# PMP30825_RevB.net
KiCad netlist of a schematic drawn in Altium Designer
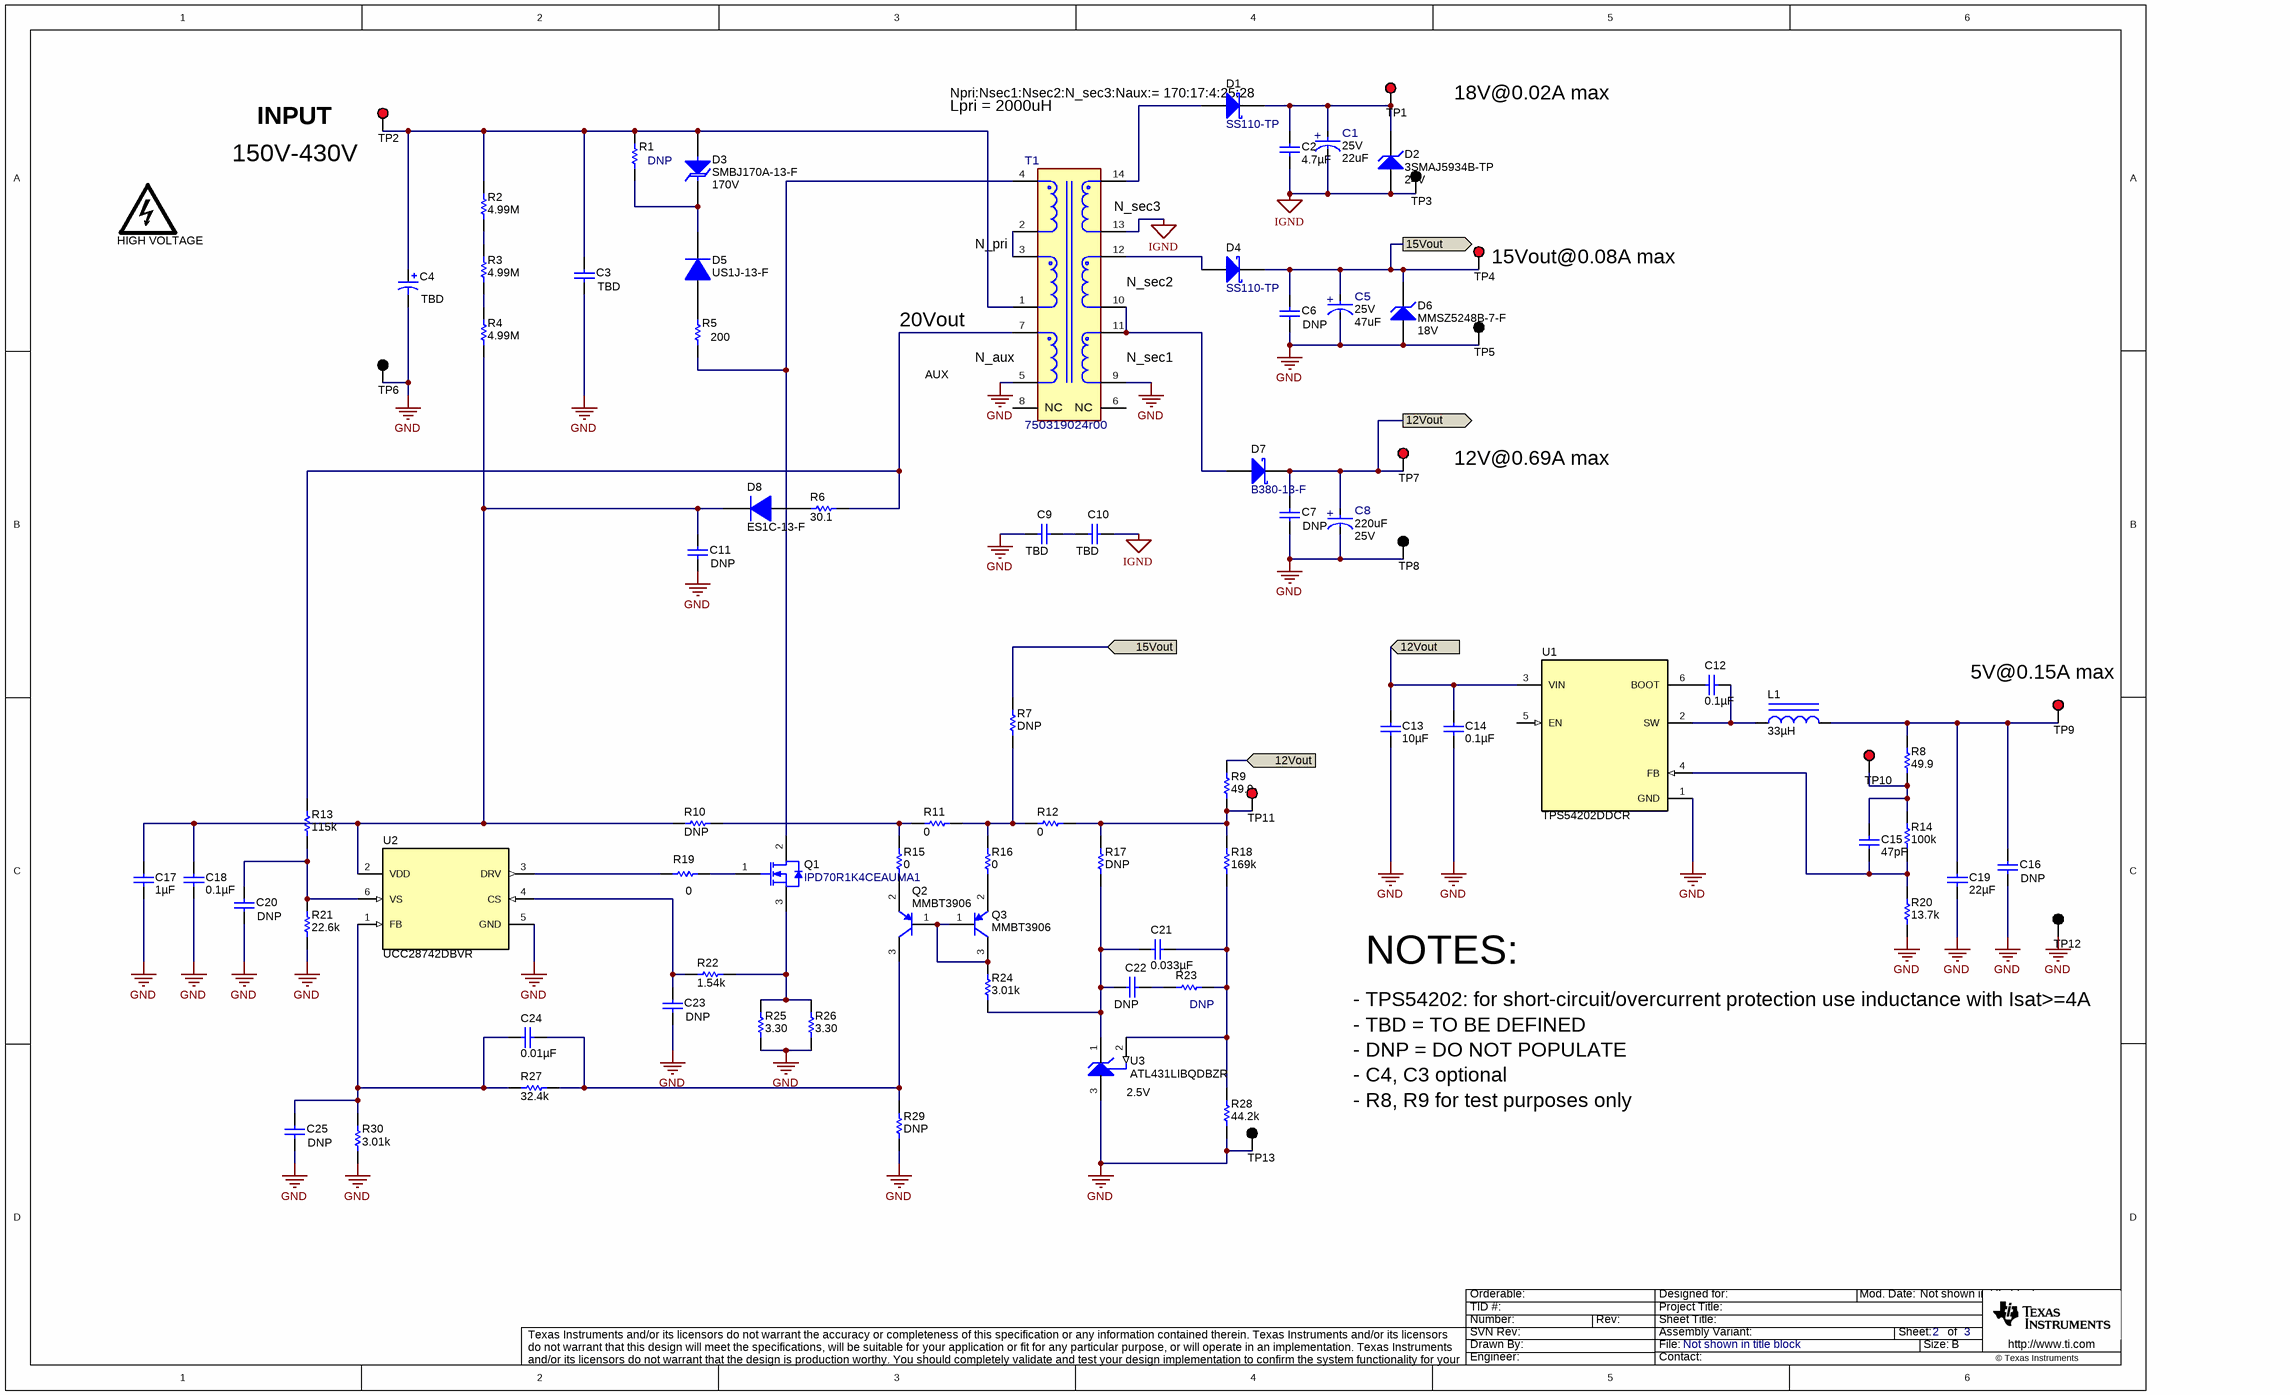
[diagram p0: PMP30825_RevB.SchDoc]

(export (version "E")
  (design (tool "Eeschema 10.0.6"))
  (components
    (comp (ref "C1")
      (value "UPW1E220MDD")
      (footprint "FP-UPW1E220MDD_RADIAL-MFG")
      (description "22uF 25 V dc Aluminium Electrolytic Capacitor, PW Series 2000h 5 (Dia.) x 11mm")
      (fields
        (field (name "MANUFACTURER") "Nichicon")
        (field (name "VDC_V") "25V")
        (field (name "VALUEDISPLAYED") "22uF")
        (field (name "MOUSER PART NUMBER") "647-UPW1E220MDD")
      )
      (libsource (lib "Altium Vault - TI") (part "SYM-UPW1E220MDD"))
    )
    (comp (ref "C2")
      (value "C3216X7R1H475K160AC")
      (footprint "1206_180")
      (description "CAP, CERM, 4.7 µF, 50 V,+/- 10%, X7R, 1206")
      (fields
        (field (name "VALUEDISPLAYED") "4.7µF")
        (field (name "MANUFACTURER") "TDK")
        (field (name "PUBLISHER") "Texas Instruments")
      )
      (libsource (lib "Capacitor_Ceramic") (part "C3216X7R1H475K160AC"))
    )
    (comp (ref "C3")
      (value "TBD")
      (footprint "2220")
      (description "CAP, CERM, 1uF,500V, [TempCo], xx%, [PackageReference]")
      (fields
        (field (name "MANUFACTURER") "Knowles Syfer")
        (field (name "PARTNUMBER") "2220Y5000105KXTWS3")
        (field (name "PUBLISHER") "Texas Instruments")
      )
      (libsource (lib "MiscParts") (part "Capacitor"))
    )
    (comp (ref "C4")
      (value "TBD")
      (footprint "ED_1250x2500")
      (description "CAP, AL, 15 µF, 450 V, +/- 20%, TH")
      (fields
        (field (name "PARTNUMBER") "EEU-ED2W150")
        (field (name "MANUFACTURER") "Panasonic")
        (field (name "PUBLISHER") "Texas Instruments")
      )
      (libsource (lib "Capacitor_Aluminum") (part "EEU-ED2W150"))
    )
    (comp (ref "C5")
      (value "25ZLG47MEFC6.3X7")
      (footprint "FP-25ZLG47MEFC6.3X7_RADIAL-MFG")
      (description "Cap Aluminum 47uF 25V 20% (6.3 X 7mm) Radial 2.5mm 480mA 1000 hr 105°C Bulk")
      (fields
        (field (name "VDC_V") "25V")
        (field (name "MANUFACTURER") "Rubycon")
        (field (name "DIGIKEY PART NUMBER") "1189-4172-ND")
        (field (name "VALUEDISPLAYED") "47uF")
      )
      (libsource (lib "Altium Vault - TI") (part "SYM-25ZLG47MEFC6.3X7"))
    )
    (comp (ref "C6")
      (value "DNP")
      (footprint "1210")
      (description "CAP, CERM, xxxF, xxV, [TempCo], xx%, [PackageReference]")
      (fields
        (field (name "MANUFACTURER") "Used in BOM report")
        (field (name "PARTNUMBER") "DNP")
        (field (name "PUBLISHER") "Texas Instruments")
      )
      (libsource (lib "MiscParts") (part "Capacitor"))
    )
    (comp (ref "C7")
      (value "DNP")
      (footprint "1210")
      (description "CAP, CERM, xxxF, xxV, [TempCo], xx%, [PackageReference]")
      (fields
        (field (name "MANUFACTURER") "Used in BOM report")
        (field (name "PARTNUMBER") "DNP")
        (field (name "PUBLISHER") "Texas Instruments")
      )
      (libsource (lib "MiscParts") (part "Capacitor"))
    )
    (comp (ref "C8")
      (value "25AX220MEFC8X9")
      (footprint "FP-25AX220MEFC8X9_RADIAL-MFG")
      (description "220µF 25V Aluminum Electrolytic Capacitors Radial, Can 2000 Hrs @ 105°C")
      (fields
        (field (name "MOUSER PART NUMBER") "232-25AX220MEFC8X9")
        (field (name "VALUEDISPLAYED") "220uF")
        (field (name "MANUFACTURER") "Rubycon")
        (field (name "VDC_V") "25V")
      )
      (libsource (lib "Altium Vault - TI") (part "SYM-25AX220MEFC8X9"))
    )
    (comp (ref "C9")
      (value "TBD")
      (footprint "KY_1000x500x1300")
      (description "CAP, CERM, 4700 pF, X1 250 VAC/Y2 300 VAC, +/- 20%, E, 10x5x13mm")
      (fields
        (field (name "PARTNUMBER") "TBD")
        (field (name "MANUFACTURER") "MuRata")
        (field (name "PUBLISHER") "Texas Instruments")
      )
      (libsource (lib "Capacitor_Ceramic") (part "DE2E3KY472MB3BM02F"))
    )
    (comp (ref "C10")
      (value "TBD")
      (footprint "KY_1000x500x1300")
      (description "CAP, CERM, 4700 pF, X1 250 VAC/Y2 300 VAC, +/- 20%, E, 10x5x13mm")
      (fields
        (field (name "PARTNUMBER") "TBD")
        (field (name "MANUFACTURER") "MuRata")
        (field (name "PUBLISHER") "Texas Instruments")
      )
      (libsource (lib "Capacitor_Ceramic") (part "DE2E3KY472MB3BM02F"))
    )
    (comp (ref "C11")
      (value "DNP")
      (footprint "1206")
      (description "CAP, CERM, xxxF, xxV, [TempCo], xx%, [PackageReference]")
      (fields
        (field (name "MANUFACTURER") "Used in BOM report")
        (field (name "PARTNUMBER") "DNP")
        (field (name "PUBLISHER") "Texas Instruments")
      )
      (libsource (lib "MiscParts") (part "Capacitor"))
    )
    (comp (ref "C12")
      (value "GRM188R71H104KA93D")
      (footprint "0603")
      (description "CAP, CERM, 0.1 µF, 50 V,+/- 10%, X7R, 0603")
      (fields
        (field (name "VALUEDISPLAYED") "0.1µF")
        (field (name "MANUFACTURER") "MuRata")
        (field (name "PUBLISHER") "Texas Instruments")
      )
      (libsource (lib "Capacitor_Ceramic") (part "GRM188R71H104KA93D"))
    )
    (comp (ref "C13")
      (value "GRM31CR71E106KA12L")
      (footprint "1206_180")
      (description "CAP, CERM, 10 µF, 25 V,+/- 10%, X7R, 1206")
      (fields
        (field (name "VALUEDISPLAYED") "10µF")
        (field (name "MANUFACTURER") "MuRata")
        (field (name "PUBLISHER") "Texas Instruments")
      )
      (libsource (lib "Capacitor_Ceramic") (part "GRM31CR71E106KA12L"))
    )
    (comp (ref "C14")
      (value "GRM188R71E104KA01D")
      (footprint "0603")
      (description "CAP, CERM, 0.1 µF, 25 V,+/- 10%, X7R, 0603")
      (fields
        (field (name "VALUEDISPLAYED") "0.1µF")
        (field (name "MANUFACTURER") "MuRata")
        (field (name "PUBLISHER") "Texas Instruments")
      )
      (libsource (lib "Capacitor_Ceramic") (part "GRM188R71E104KA01D"))
    )
    (comp (ref "C15")
      (value "GRM1885C1H470JA01D")
      (footprint "0603")
      (description "CAP, CERM, 47 pF, 50 V,+/- 5%, C0G/NP0, 0603")
      (fields
        (field (name "VALUEDISPLAYED") "47pF")
        (field (name "MANUFACTURER") "MuRata")
        (field (name "PUBLISHER") "Texas Instruments")
      )
      (libsource (lib "Capacitor_Ceramic") (part "GRM1885C1H470JA01D"))
    )
    (comp (ref "C16")
      (value "DNP")
      (footprint "1206")
      (description "CAP, CERM, xxxF, xxV, [TempCo], xx%, [PackageReference]")
      (fields
        (field (name "MANUFACTURER") "Used in BOM report")
        (field (name "PUBLISHER") "Texas Instruments")
      )
      (libsource (lib "MiscParts") (part "Capacitor"))
    )
    (comp (ref "C17")
      (value "GRM21BR71H105KA12L")
      (footprint "0805_HV1")
      (description "CAP, CERM, 1 µF, 50 V,+/- 10%, X7R, 0805")
      (fields
        (field (name "VALUEDISPLAYED") "1µF")
        (field (name "MANUFACTURER") "MuRata")
        (field (name "PUBLISHER") "Texas Instruments")
      )
      (libsource (lib "Capacitor_Ceramic") (part "GRM21BR71H105KA12L"))
    )
    (comp (ref "C18")
      (value "C0805C104J5RACTU")
      (footprint "0805_HV1")
      (description "CAP, CERM, 0.1 µF, 50 V,+/- 5%, X7R, 0805")
      (fields
        (field (name "VALUEDISPLAYED") "0.1µF")
        (field (name "MANUFACTURER") "Kemet")
        (field (name "PUBLISHER") "Texas Instruments")
      )
      (libsource (lib "Capacitor_Ceramic") (part "C0805C104J5RACTU"))
    )
    (comp (ref "C19")
      (value "GRM31CR71A226KE15L")
      (footprint "1206_180")
      (description "CAP, CERM, 22 µF, 10 V,+/- 10%, X7R, 1206")
      (fields
        (field (name "VALUEDISPLAYED") "22µF")
        (field (name "MANUFACTURER") "MuRata")
        (field (name "PUBLISHER") "Texas Instruments")
      )
      (libsource (lib "Capacitor_Ceramic") (part "GRM31CR71A226KE15L"))
    )
    (comp (ref "C20")
      (value "DNP")
      (footprint "0603")
      (description "CAP, CERM, xxxF, xxV, [TempCo], xx%, [PackageReference]")
      (fields
        (field (name "MANUFACTURER") "Used in BOM report")
        (field (name "PUBLISHER") "Texas Instruments")
      )
      (libsource (lib "MiscParts") (part "Capacitor"))
    )
    (comp (ref "C21")
      (value "08055C333JAT2A")
      (footprint "0805_HV")
      (description "CAP, CERM, 0.033 µF, 50 V,+/- 5%, X7R, 0805")
      (fields
        (field (name "VALUEDISPLAYED") "0.033µF")
        (field (name "MANUFACTURER") "AVX")
        (field (name "PUBLISHER") "Texas Instruments")
      )
      (libsource (lib "Capacitor_Ceramic") (part "08055C333JAT2A"))
    )
    (comp (ref "C22")
      (value "DNP")
      (footprint "0805")
      (description "CAP, CERM, xxxF, xxV, [TempCo], xx%, [PackageReference]")
      (fields
        (field (name "MANUFACTURER") "Used in BOM report")
        (field (name "PUBLISHER") "Texas Instruments")
      )
      (libsource (lib "MiscParts") (part "Capacitor"))
    )
    (comp (ref "C23")
      (value "DNP")
      (footprint "0603")
      (description "CAP, CERM, xxxF, xxV, [TempCo], xx%, [PackageReference]")
      (fields
        (field (name "MANUFACTURER") "Used in BOM report")
        (field (name "PUBLISHER") "Texas Instruments")
      )
      (libsource (lib "MiscParts") (part "Capacitor"))
    )
    (comp (ref "C24")
      (value "C0603X103K5RACTU")
      (footprint "0603")
      (description "CAP, CERM, 0.01 µF, 50 V,+/- 10%, X7R, 0603")
      (fields
        (field (name "VALUEDISPLAYED") "0.01µF")
        (field (name "MANUFACTURER") "Kemet")
        (field (name "PUBLISHER") "Texas Instruments")
      )
      (libsource (lib "Capacitor_Ceramic") (part "C0603X103K5RACTU"))
    )
    (comp (ref "C25")
      (value "DNP")
      (footprint "0603")
      (description "CAP, CERM, xxxF, xxV, [TempCo], xx%, [PackageReference]")
      (fields
        (field (name "MANUFACTURER") "Used in BOM report")
        (field (name "PUBLISHER") "Texas Instruments")
      )
      (libsource (lib "MiscParts") (part "Capacitor"))
    )
    (comp (ref "D1")
      (value "SS110-TP")
      (footprint "SMA")
      (description "Diode, Schottky, 100 V, 1 A, SMA")
      (fields (field (name "MANUFACTURER") "Micro Commercial Components"))
      (libsource (lib "Altium Vault - TI") (part "DIODE_SCHOTTKY"))
    )
    (comp (ref "D2")
      (value "3SMAJ5934B-TP")
      (footprint "SMA")
      (description "Diode, Zener, 24 V, 3 W, SMA")
      (fields
        (field (name "ALTIUM_VALUE") "24V")
        (field (name "MANUFACTURER") "Micro Commercial Components")
        (field (name "SYMBOLCREATOR") "a0412235")
        (field (name "PUBLISHER") "Texas Instruments")
      )
      (libsource (lib "ZenerDiodes") (part "3SMAJ5934B-TP"))
    )
    (comp (ref "D3")
      (value "SMBJ170A-13-F")
      (footprint "SMB")
      (description "Diode, TVS, Uni, 170 V, 275 Vc, SMB")
      (fields
        (field (name "ALTIUM_VALUE") "170V")
        (field (name "MANUFACTURER") "Diodes Inc.")
        (field (name "PUBLISHER") "Texas Instruments")
      )
      (libsource (lib "ZenerDiodes") (part "SMBJ170A-13-F"))
    )
    (comp (ref "D4")
      (value "SS110-TP")
      (footprint "SMA")
      (description "Diode, Schottky, 100 V, 1 A, SMA")
      (fields (field (name "MANUFACTURER") "Micro Commercial Components"))
      (libsource (lib "Altium Vault - TI") (part "DIODE_SCHOTTKY"))
    )
    (comp (ref "D5")
      (value "US1J-13-F")
      (footprint "SMA")
      (description "Diode, Ultrafast, 600 V, 1 A, SMA")
      (fields (field (name "MANUFACTURER") "Diodes Inc.") (field (name "PUBLISHER") "Texas Instruments"))
      (libsource (lib "Diode") (part "US1J-13-F"))
    )
    (comp (ref "D6")
      (value "MMSZ5248B-7-F")
      (footprint "SOD-123")
      (description "Diode, Zener, 18 V, 500 mW, SOD-123")
      (fields
        (field (name "ALTIUM_VALUE") "18V")
        (field (name "MANUFACTURER") "Diodes Inc.")
        (field (name "SYMBOLCREATOR") "a0412235")
        (field (name "PUBLISHER") "Texas Instruments")
      )
      (libsource (lib "ZenerDiodes") (part "MMSZ5248B-7-F"))
    )
    (comp (ref "D7")
      (value "B380-13-F")
      (footprint "SMC")
      (description "Diode, Schottky, 80 V, 3 A, SMC")
      (fields (field (name "MANUFACTURER") "Diodes Inc.") (field (name "PUBLISHER") "Texas Instruments"))
      (libsource (lib "Altium Vault - TI") (part "DIODE_SCHOTTKY"))
    )
    (comp (ref "D8")
      (value "ES1C-13-F")
      (footprint "SMA")
      (description "Diode, Superfast Rectifier, 150 V, 1 A, SMA")
      (fields (field (name "MANUFACTURER") "Diodes Inc.") (field (name "PUBLISHER") "Texas Instruments"))
      (libsource (lib "Diode") (part "ES1C-13-F"))
    )
    (comp (ref "HIGH VOLTAGE")
      (value "DANGER HIGH VOLTAGE")
      (footprint "IEC_HighVoltage_Small")
      (description "IEC 61010-1 High Voltage Warning")
      (fields (field (name "SYMBOLCREATOR") "a0412235") (field (name "PUBLISHER") "Texas Instruments"))
      (libsource (lib "Logos") (part "IEC_HighVoltage"))
    )
    (comp (ref "L1")
      (value "LPS4018-333MLB")
      (footprint "LPS4018")
      (description "Inductor, Shielded Drum Core, Ferrite, 33 µH, 0.68 A, 0.42 ohm, SMD")
      (fields
        (field (name "VALUEDISPLAYED") "33µH")
        (field (name "MANUFACTURER") "Coilcraft")
        (field (name "PUBLISHER") "Texas Instruments")
      )
      (libsource (lib "Inductor_Coilcraft") (part "LPS4018-333MLB"))
    )
    (comp (ref "Q1")
      (value "IPD70R1K4CEAUMA1")
      (footprint "DPAK")
      (description "MOSFET, N-CH, 750 V, 5.4 A, DPAK")
      (fields (field (name "MANUFACTURER") "Infineon Technologies"))
      (libsource (lib "Altium Vault - TI") (part "MOSFET_N_D2G1S3"))
    )
    (comp (ref "Q2")
      (value "MMBT3906")
      (footprint "SOT-23")
      (description "Transistor, PNP, 40 V, 0.2 A, SOT-23")
      (fields
        (field (name "MANUFACTURER") "Fairchild Semiconductor")
        (field (name "PUBLISHER") "Texas Instruments")
      )
      (libsource (lib "Bipolar_Transistor") (part "MMBT3906, Fairchild Semiconductor"))
    )
    (comp (ref "Q3")
      (value "MMBT3906")
      (footprint "SOT-23")
      (description "Transistor, PNP, 40 V, 0.2 A, SOT-23")
      (fields
        (field (name "MANUFACTURER") "Fairchild Semiconductor")
        (field (name "PUBLISHER") "Texas Instruments")
      )
      (libsource (lib "Bipolar_Transistor") (part "MMBT3906, Fairchild Semiconductor"))
    )
    (comp (ref "R1")
      (value "DNP")
      (footprint "2512")
      (description "RES, xxx ohm, x%, xW, [PackageReference]")
      (fields
        (field (name "MANUFACTURER") "Used in BOM report")
        (field (name "PUBLISHER") "Texas Instruments")
      )
      (libsource (lib "MiscParts") (part "Resistor"))
    )
    (comp (ref "R2")
      (value "CRCW08054M99FKEA")
      (footprint "0805_HV")
      (description "RES, 4.99 M, 1%, 0.125 W, 0805")
      (fields
        (field (name "VALUEDISPLAYED") "4.99M")
        (field (name "MANUFACTURER") "Vishay-Dale")
        (field (name "PUBLISHER") "Texas Instruments")
      )
      (libsource (lib "Resistor_0805") (part "CRCW08054M99FKEA"))
    )
    (comp (ref "R3")
      (value "CRCW08054M99FKEA")
      (footprint "0805_HV")
      (description "RES, 4.99 M, 1%, 0.125 W, 0805")
      (fields
        (field (name "VALUEDISPLAYED") "4.99M")
        (field (name "MANUFACTURER") "Vishay-Dale")
        (field (name "PUBLISHER") "Texas Instruments")
      )
      (libsource (lib "Resistor_0805") (part "CRCW08054M99FKEA"))
    )
    (comp (ref "R4")
      (value "CRCW08054M99FKEA")
      (footprint "0805_HV")
      (description "RES, 4.99 M, 1%, 0.125 W, 0805")
      (fields
        (field (name "VALUEDISPLAYED") "4.99M")
        (field (name "MANUFACTURER") "Vishay-Dale")
        (field (name "PUBLISHER") "Texas Instruments")
      )
      (libsource (lib "Resistor_0805") (part "CRCW08054M99FKEA"))
    )
    (comp (ref "R5")
      (value "200")
      (footprint "2512")
      (description "RES, 200, 5%, 1 W, AEC-Q200 Grade 0, 2512")
      (fields
        (field (name "PARTNUMBER") "CRCW2512200RJNEG")
        (field (name "MANUFACTURER") "Vishay-Dale")
        (field (name "PUBLISHER") "Texas Instruments")
      )
      (libsource (lib "Resistor_2512") (part "CRCW2512200RJNEG"))
    )
    (comp (ref "R6")
      (value "CRCW080530R1FKEA")
      (footprint "0805_HV")
      (description "RES, 30.1, 1%, 0.125 W, 0805")
      (fields
        (field (name "VALUEDISPLAYED") "30.1")
        (field (name "MANUFACTURER") "Vishay-Dale")
        (field (name "PUBLISHER") "Texas Instruments")
      )
      (libsource (lib "Resistor_0805") (part "CRCW080530R1FKEA"))
    )
    (comp (ref "R7")
      (value "DNP")
      (footprint "0603")
      (description "RES, xxx ohm, x%, xW, [PackageReference]")
      (fields
        (field (name "MANUFACTURER") "Used in BOM report")
        (field (name "PUBLISHER") "Texas Instruments")
      )
      (libsource (lib "MiscParts") (part "Resistor"))
    )
    (comp (ref "R8")
      (value "CRCW060349R9FKEA")
      (footprint "0603")
      (description "RES, 49.9, 1%, 0.1 W, 0603")
      (fields
        (field (name "VALUEDISPLAYED") "49.9")
        (field (name "MANUFACTURER") "Vishay-Dale")
        (field (name "PUBLISHER") "Texas Instruments")
      )
      (libsource (lib "Resistor_0603") (part "CRCW060349R9FKEA"))
    )
    (comp (ref "R9")
      (value "CRCW060349R9FKEA")
      (footprint "0603")
      (description "RES, 49.9, 1%, 0.1 W, 0603")
      (fields
        (field (name "VALUEDISPLAYED") "49.9")
        (field (name "MANUFACTURER") "Vishay-Dale")
        (field (name "PUBLISHER") "Texas Instruments")
      )
      (libsource (lib "Resistor_0603") (part "CRCW060349R9FKEA"))
    )
    (comp (ref "R10")
      (value "DNP")
      (footprint "0603")
      (description "RES, xxx ohm, x%, xW, [PackageReference]")
      (fields
        (field (name "MANUFACTURER") "Used in BOM report")
        (field (name "PUBLISHER") "Texas Instruments")
      )
      (libsource (lib "MiscParts") (part "Resistor"))
    )
    (comp (ref "R11")
      (value "CRCW06030000Z0EA")
      (footprint "0603")
      (description "RES, 0, 5%, 0.1 W, 0603")
      (fields
        (field (name "VALUEDISPLAYED") "0")
        (field (name "MANUFACTURER") "Vishay-Dale")
        (field (name "PUBLISHER") "Texas Instruments")
      )
      (libsource (lib "Resistor_0603") (part "CRCW06030000Z0EA"))
    )
    (comp (ref "R12")
      (value "CRCW06030000Z0EA")
      (footprint "0603")
      (description "RES, 0, 5%, 0.1 W, 0603")
      (fields
        (field (name "VALUEDISPLAYED") "0")
        (field (name "MANUFACTURER") "Vishay-Dale")
        (field (name "PUBLISHER") "Texas Instruments")
      )
      (libsource (lib "Resistor_0603") (part "CRCW06030000Z0EA"))
    )
    (comp (ref "R13")
      (value "CRCW0603115KFKEA")
      (footprint "0603")
      (description "RES, 115 k, 1%, 0.1 W, 0603")
      (fields
        (field (name "VALUEDISPLAYED") "115k")
        (field (name "MANUFACTURER") "Vishay-Dale")
        (field (name "PUBLISHER") "Texas Instruments")
      )
      (libsource (lib "Resistor_0603") (part "CRCW0603115KFKEA"))
    )
    (comp (ref "R14")
      (value "CRCW0603100KFKEA")
      (footprint "0603")
      (description "RES, 100 k, 1%, 0.1 W, 0603")
      (fields
        (field (name "VALUEDISPLAYED") "100k")
        (field (name "MANUFACTURER") "Vishay-Dale")
        (field (name "PUBLISHER") "Texas Instruments")
      )
      (libsource (lib "Resistor_0603") (part "CRCW0603100KFKEA"))
    )
    (comp (ref "R15")
      (value "CRCW06030000Z0EA")
      (footprint "0603")
      (description "RES, 0, 5%, 0.1 W, 0603")
      (fields
        (field (name "VALUEDISPLAYED") "0")
        (field (name "MANUFACTURER") "Vishay-Dale")
        (field (name "PUBLISHER") "Texas Instruments")
      )
      (libsource (lib "Resistor_0603") (part "CRCW06030000Z0EA"))
    )
    (comp (ref "R16")
      (value "CRCW06030000Z0EA")
      (footprint "0603")
      (description "RES, 0, 5%, 0.1 W, 0603")
      (fields
        (field (name "VALUEDISPLAYED") "0")
        (field (name "MANUFACTURER") "Vishay-Dale")
        (field (name "PUBLISHER") "Texas Instruments")
      )
      (libsource (lib "Resistor_0603") (part "CRCW06030000Z0EA"))
    )
    (comp (ref "R17")
      (value "DNP")
      (footprint "0603")
      (description "RES, xxx ohm, x%, xW, [PackageReference]")
      (fields
        (field (name "MANUFACTURER") "Used in BOM report")
        (field (name "PUBLISHER") "Texas Instruments")
      )
      (libsource (lib "MiscParts") (part "Resistor"))
    )
    (comp (ref "R18")
      (value "CRCW0603169KFKEA")
      (footprint "0603")
      (description "RES, 169 k, 1%, 0.1 W, 0603")
      (fields
        (field (name "VALUEDISPLAYED") "169k")
        (field (name "MANUFACTURER") "Vishay-Dale")
        (field (name "PUBLISHER") "Texas Instruments")
      )
      (libsource (lib "Resistor_0603") (part "CRCW0603169KFKEA"))
    )
    (comp (ref "R19")
      (value "CRCW08050000Z0EA")
      (footprint "0805_HV")
      (description "RES, 0, 5%, 0.125 W, 0805")
      (fields
        (field (name "VALUEDISPLAYED") "0")
        (field (name "MANUFACTURER") "Vishay-Dale")
        (field (name "PUBLISHER") "Texas Instruments")
      )
      (libsource (lib "Resistor_0805") (part "CRCW08050000Z0EA"))
    )
    (comp (ref "R20")
      (value "CRCW060313K7FKEA")
      (footprint "0603")
      (description "RES, 13.7 k, 1%, 0.1 W, 0603")
      (fields
        (field (name "VALUEDISPLAYED") "13.7k")
        (field (name "MANUFACTURER") "Vishay-Dale")
        (field (name "PUBLISHER") "Texas Instruments")
      )
      (libsource (lib "Resistor_0603") (part "CRCW060313K7FKEA"))
    )
    (comp (ref "R21")
      (value "CRCW060322K6FKEA")
      (footprint "0603")
      (description "RES, 22.6 k, 1%, 0.1 W, 0603")
      (fields
        (field (name "VALUEDISPLAYED") "22.6k")
        (field (name "MANUFACTURER") "Vishay-Dale")
        (field (name "PUBLISHER") "Texas Instruments")
      )
      (libsource (lib "Resistor_0603") (part "CRCW060322K6FKEA"))
    )
    (comp (ref "R22")
      (value "CRCW06031K54FKEA")
      (footprint "0603")
      (description "RES, 1.54 k, 1%, 0.1 W, 0603")
      (fields
        (field (name "VALUEDISPLAYED") "1.54k")
        (field (name "MANUFACTURER") "Vishay-Dale")
        (field (name "PUBLISHER") "Texas Instruments")
      )
      (libsource (lib "Resistor_0603") (part "CRCW06031K54FKEA"))
    )
    (comp (ref "R23")
      (value "DNP")
      (footprint "0603")
      (description "RES, xxx ohm, x%, xW, [PackageReference]")
      (fields
        (field (name "MANUFACTURER") "Used in BOM report")
        (field (name "PUBLISHER") "Texas Instruments")
      )
      (libsource (lib "MiscParts") (part "Resistor"))
    )
    (comp (ref "R24")
      (value "CRCW06033K01FKEA")
      (footprint "0603")
      (description "RES, 3.01 k, 1%, 0.1 W, 0603")
      (fields
        (field (name "VALUEDISPLAYED") "3.01k")
        (field (name "MANUFACTURER") "Vishay-Dale")
        (field (name "PUBLISHER") "Texas Instruments")
      )
      (libsource (lib "Resistor_0603") (part "CRCW06033K01FKEA"))
    )
    (comp (ref "R25")
      (value "ERJ-6RQF3R3V")
      (footprint "0805_HV")
      (description "RES, 3.30, 1%, 0.125 W, 0805")
      (fields
        (field (name "VALUEDISPLAYED") "3.30")
        (field (name "MANUFACTURER") "Panasonic")
        (field (name "PUBLISHER") "Texas Instruments")
      )
      (libsource (lib "Resistor_0805") (part "ERJ-6RQF3R3V"))
    )
    (comp (ref "R26")
      (value "ERJ-6RQF3R3V")
      (footprint "0805_HV")
      (description "RES, 3.30, 1%, 0.125 W, 0805")
      (fields
        (field (name "VALUEDISPLAYED") "3.30")
        (field (name "MANUFACTURER") "Panasonic")
        (field (name "PUBLISHER") "Texas Instruments")
      )
      (libsource (lib "Resistor_0805") (part "ERJ-6RQF3R3V"))
    )
    (comp (ref "R27")
      (value "CRCW060332K4FKEA")
      (footprint "0603")
      (description "RES, 32.4 k, 1%, 0.1 W, 0603")
      (fields
        (field (name "VALUEDISPLAYED") "32.4k")
        (field (name "MANUFACTURER") "Vishay-Dale")
        (field (name "PUBLISHER") "Texas Instruments")
      )
      (libsource (lib "Resistor_0603") (part "CRCW060332K4FKEA"))
    )
    (comp (ref "R28")
      (value "CRCW060344K2FKEA")
      (footprint "0603")
      (description "RES, 44.2 k, 1%, 0.1 W, 0603")
      (fields
        (field (name "VALUEDISPLAYED") "44.2k")
        (field (name "MANUFACTURER") "Vishay-Dale")
        (field (name "PUBLISHER") "Texas Instruments")
      )
      (libsource (lib "Resistor_0603") (part "CRCW060344K2FKEA"))
    )
    (comp (ref "R29")
      (value "DNP")
      (footprint "0603")
      (description "RES, xxx ohm, x%, xW, [PackageReference]")
      (fields
        (field (name "MANUFACTURER") "Used in BOM report")
        (field (name "PUBLISHER") "Texas Instruments")
      )
      (libsource (lib "MiscParts") (part "Resistor"))
    )
    (comp (ref "R30")
      (value "CRCW06033K01FKEA")
      (footprint "0603")
      (description "RES, 3.01 k, 1%, 0.1 W, 0603")
      (fields
        (field (name "VALUEDISPLAYED") "3.01k")
        (field (name "MANUFACTURER") "Vishay-Dale")
        (field (name "PUBLISHER") "Texas Instruments")
      )
      (libsource (lib "Resistor_0603") (part "CRCW06033K01FKEA"))
    )
    (comp (ref "T1")
      (value "750319024r00")
      (footprint "FP-750319024r00_PTH_TRANSFORMER-MFG")
      (description "TRANSFORMER")
      (fields (field (name "MANUFACTURER") "Wurth Electronics"))
      (libsource (lib "Altium Vault - TI") (part "SYM-750319024r00"))
    )
    (comp (ref "TP1")
      (value "5000")
      (footprint "Keystone5000")
      (description "Test Point, Miniature, Red, TH")
      (fields (field (name "MANUFACTURER") "Keystone") (field (name "PUBLISHER") "Texas Instruments"))
      (libsource (lib "Connectors_Keystone") (part "5000"))
    )
    (comp (ref "TP2")
      (value "5000")
      (footprint "Keystone5000")
      (description "Test Point, Miniature, Red, TH")
      (fields (field (name "MANUFACTURER") "Keystone") (field (name "PUBLISHER") "Texas Instruments"))
      (libsource (lib "Connectors_Keystone") (part "5000"))
    )
    (comp (ref "TP3")
      (value "5001")
      (footprint "Keystone5001")
      (description "Test Point, Miniature, Black, TH")
      (fields (field (name "MANUFACTURER") "Keystone") (field (name "PUBLISHER") "Texas Instruments"))
      (libsource (lib "Connectors_Keystone") (part "5001"))
    )
    (comp (ref "TP4")
      (value "5000")
      (footprint "Keystone5000")
      (description "Test Point, Miniature, Red, TH")
      (fields (field (name "MANUFACTURER") "Keystone") (field (name "PUBLISHER") "Texas Instruments"))
      (libsource (lib "Connectors_Keystone") (part "5000"))
    )
    (comp (ref "TP5")
      (value "5001")
      (footprint "Keystone5001")
      (description "Test Point, Miniature, Black, TH")
      (fields (field (name "MANUFACTURER") "Keystone") (field (name "PUBLISHER") "Texas Instruments"))
      (libsource (lib "Connectors_Keystone") (part "5001"))
    )
    (comp (ref "TP6")
      (value "5001")
      (footprint "Keystone5001")
      (description "Test Point, Miniature, Black, TH")
      (fields (field (name "MANUFACTURER") "Keystone") (field (name "PUBLISHER") "Texas Instruments"))
      (libsource (lib "Connectors_Keystone") (part "5001"))
    )
    (comp (ref "TP7")
      (value "5000")
      (footprint "Keystone5000")
      (description "Test Point, Miniature, Red, TH")
      (fields (field (name "MANUFACTURER") "Keystone") (field (name "PUBLISHER") "Texas Instruments"))
      (libsource (lib "Connectors_Keystone") (part "5000"))
    )
    (comp (ref "TP8")
      (value "5001")
      (footprint "Keystone5001")
      (description "Test Point, Miniature, Black, TH")
      (fields (field (name "MANUFACTURER") "Keystone") (field (name "PUBLISHER") "Texas Instruments"))
      (libsource (lib "Connectors_Keystone") (part "5001"))
    )
    (comp (ref "TP9")
      (value "5000")
      (footprint "Keystone5000")
      (description "Test Point, Miniature, Red, TH")
      (fields (field (name "MANUFACTURER") "Keystone") (field (name "PUBLISHER") "Texas Instruments"))
      (libsource (lib "Connectors_Keystone") (part "5000"))
    )
    (comp (ref "TP10")
      (value "5000")
      (footprint "Keystone5000")
      (description "Test Point, Miniature, Red, TH")
      (fields (field (name "MANUFACTURER") "Keystone") (field (name "PUBLISHER") "Texas Instruments"))
      (libsource (lib "Connectors_Keystone") (part "5000"))
    )
    (comp (ref "TP11")
      (value "5000")
      (footprint "Keystone5000")
      (description "Test Point, Miniature, Red, TH")
      (fields (field (name "MANUFACTURER") "Keystone") (field (name "PUBLISHER") "Texas Instruments"))
      (libsource (lib "Connectors_Keystone") (part "5000"))
    )
    (comp (ref "TP12")
      (value "5001")
      (footprint "Keystone5001")
      (description "Test Point, Miniature, Black, TH")
      (fields (field (name "MANUFACTURER") "Keystone") (field (name "PUBLISHER") "Texas Instruments"))
      (libsource (lib "Connectors_Keystone") (part "5001"))
    )
    (comp (ref "TP13")
      (value "5001")
      (footprint "Keystone5001")
      (description "Test Point, Miniature, Black, TH")
      (fields (field (name "MANUFACTURER") "Keystone") (field (name "PUBLISHER") "Texas Instruments"))
      (libsource (lib "Connectors_Keystone") (part "5001"))
    )
    (comp (ref "U1")
      (value "TPS54202DDCR")
      (footprint "DDC0006A_N")
      (fields
        (field (name "ALTERNATE PARTNUMBER") "TPS54202DDCT")
        (field (name "MANUFACTURER") "Texas Instruments")
        (field (name "PARTNUMBER") "TPS54202DDCR")
      )
      (libsource (lib "Altium Vault - TI") (part "TPS54202"))
    )
    (comp (ref "U2")
      (value "UCC28742DBVR")
      (footprint "DBV0006A_N")
      (description "High-Efficiency Low-Cost Flyback Controller with Secondary-Side Regulation, DBV0006A (SOT-23-6)")
      (fields (field (name "PARTNUMBER") "UCC28742DBVR") (field (name "MANUFACTURER") "Texas Instruments"))
      (libsource (lib "Altium Vault - TI") (part "UCC28742"))
    )
    (comp (ref "U3")
      (value "ATL431LIBQDBZR")
      (footprint "DBZ0003A_N")
      (description "High Bandwidth Low-Iq Programmable Shunt Regulator, DBZ0003A (SOT-23-3)")
      (fields (field (name "MANUFACTURER") "Texas Instruments") (field (name "PARTNUMBER") "ATL431LIBQDBZR"))
      (libsource (lib "Altium Vault - TI") (part "TL431DBZ"))
    )
  )
  (nets
    (net (code "1") (name "/12Vout") (class "Default")
      (node (ref "C13") (pin "1") (pinfunction "1_1") (pintype "passive"))
      (node (ref "C14") (pin "1") (pinfunction "1_1") (pintype "passive"))
      (node (ref "C7") (pin "1") (pinfunction "1_1") (pintype "passive"))
      (node (ref "C8") (pin "2") (pinfunction "ANODE_2") (pintype "passive"))
      (node (ref "D7") (pin "1") (pinfunction "K_1") (pintype "passive"))
      (node (ref "R9") (pin "2") (pinfunction "2_2") (pintype "passive"))
      (node (ref "TP7") (pin "1") (pintype "passive"))
      (node (ref "U1") (pin "3") (pinfunction "VIN_3") (pintype "power_in"))
    )
    (net (code "2") (name "/15Vout") (class "Default")
      (node (ref "C5") (pin "2") (pinfunction "ANODE_2") (pintype "passive"))
      (node (ref "C6") (pin "1") (pinfunction "1_1") (pintype "passive"))
      (node (ref "D4") (pin "1") (pinfunction "K_1") (pintype "passive"))
      (node (ref "D6") (pin "1") (pinfunction "K_1") (pintype "passive"))
      (node (ref "R7") (pin "1") (pinfunction "1_1") (pintype "passive"))
      (node (ref "TP4") (pin "1") (pintype "passive"))
    )
    (net (code "3") (name "GND") (class "Default")
      (node (ref "C11") (pin "2") (pinfunction "2_2") (pintype "passive"))
      (node (ref "C13") (pin "2") (pinfunction "2_2") (pintype "passive"))
      (node (ref "C14") (pin "2") (pinfunction "2_2") (pintype "passive"))
      (node (ref "C16") (pin "2") (pinfunction "2_2") (pintype "passive"))
      (node (ref "C17") (pin "2") (pinfunction "2_2") (pintype "passive"))
      (node (ref "C18") (pin "2") (pinfunction "2_2") (pintype "passive"))
      (node (ref "C19") (pin "2") (pinfunction "2_2") (pintype "passive"))
      (node (ref "C20") (pin "2") (pinfunction "2_2") (pintype "passive"))
      (node (ref "C23") (pin "2") (pinfunction "2_2") (pintype "passive"))
      (node (ref "C25") (pin "2") (pinfunction "2_2") (pintype "passive"))
      (node (ref "C3") (pin "2") (pinfunction "2_2") (pintype "passive"))
      (node (ref "C4") (pin "2") (pinfunction "-_2") (pintype "passive"))
      (node (ref "C5") (pin "1") (pinfunction "CATHODE_1") (pintype "passive"))
      (node (ref "C6") (pin "2") (pinfunction "2_2") (pintype "passive"))
      (node (ref "C7") (pin "2") (pinfunction "2_2") (pintype "passive"))
      (node (ref "C8") (pin "1") (pinfunction "CATHODE_1") (pintype "passive"))
      (node (ref "C9") (pin "2") (pinfunction "2_2") (pintype "passive"))
      (node (ref "D6") (pin "2") (pinfunction "A_2") (pintype "passive"))
      (node (ref "R20") (pin "1") (pinfunction "1_1") (pintype "passive"))
      (node (ref "R21") (pin "1") (pinfunction "1_1") (pintype "passive"))
      (node (ref "R25") (pin "1") (pinfunction "1_1") (pintype "passive"))
      (node (ref "R26") (pin "1") (pinfunction "1_1") (pintype "passive"))
      (node (ref "R28") (pin "1") (pinfunction "1_1") (pintype "passive"))
      (node (ref "R29") (pin "2") (pinfunction "2_2") (pintype "passive"))
      (node (ref "R30") (pin "1") (pinfunction "1_1") (pintype "passive"))
      (node (ref "T1") (pin "5") (pinfunction "5_5") (pintype "passive"))
      (node (ref "T1") (pin "9") (pinfunction "9_9") (pintype "passive"))
      (node (ref "TP12") (pin "1") (pintype "passive"))
      (node (ref "TP13") (pin "1") (pintype "passive"))
      (node (ref "TP5") (pin "1") (pintype "passive"))
      (node (ref "TP6") (pin "1") (pintype "passive"))
      (node (ref "TP8") (pin "1") (pintype "passive"))
      (node (ref "U1") (pin "1") (pinfunction "GND_1") (pintype "power_in"))
      (node (ref "U2") (pin "5") (pinfunction "GND_5") (pintype "power_in"))
      (node (ref "U3") (pin "3") (pinfunction "ANODE_3") (pintype "passive"))
    )
    (net (code "4") (name "IGND") (class "Default")
      (node (ref "C1") (pin "1") (pinfunction "CATHODE_1") (pintype "passive"))
      (node (ref "C10") (pin "1") (pinfunction "1_1") (pintype "passive"))
      (node (ref "C2") (pin "2") (pinfunction "2_2") (pintype "passive"))
      (node (ref "D2") (pin "2") (pinfunction "A_2") (pintype "passive"))
      (node (ref "T1") (pin "13") (pinfunction "13_13") (pintype "passive"))
      (node (ref "TP3") (pin "1") (pintype "passive"))
    )
    (net (code "5") (name "Net-(C1-ANODE)") (class "Default")
      (node (ref "C1") (pin "2") (pinfunction "ANODE_2") (pintype "passive"))
      (node (ref "C2") (pin "1") (pinfunction "1_1") (pintype "passive"))
      (node (ref "D1") (pin "1") (pinfunction "K_1") (pintype "passive"))
      (node (ref "D2") (pin "1") (pinfunction "K_1") (pintype "passive"))
      (node (ref "TP1") (pin "1") (pintype "passive"))
    )
    (net (code "6") (name "Net-(C4-+)") (class "Default")
      (node (ref "C3") (pin "1") (pinfunction "1_1") (pintype "passive"))
      (node (ref "C4") (pin "1") (pinfunction "+_1") (pintype "passive"))
      (node (ref "D3") (pin "2") (pinfunction "A_2") (pintype "passive"))
      (node (ref "R1") (pin "2") (pinfunction "2_2") (pintype "passive"))
      (node (ref "R2") (pin "2") (pinfunction "2_2") (pintype "passive"))
      (node (ref "T1") (pin "1") (pinfunction "1_1") (pintype "passive"))
      (node (ref "TP2") (pin "1") (pintype "passive"))
    )
    (net (code "7") (name "Net-(C10-Pad2)") (class "Default")
      (node (ref "C10") (pin "2") (pinfunction "2_2") (pintype "passive"))
      (node (ref "C9") (pin "1") (pinfunction "1_1") (pintype "passive"))
    )
    (net (code "8") (name "Net-(C15-Pad1)") (class "Default")
      (node (ref "C15") (pin "1") (pinfunction "1_1") (pintype "passive"))
      (node (ref "R14") (pin "2") (pinfunction "2_2") (pintype "passive"))
      (node (ref "R8") (pin "1") (pinfunction "1_1") (pintype "passive"))
      (node (ref "TP10") (pin "1") (pintype "passive"))
    )
    (net (code "9") (name "Net-(C16-Pad1)") (class "Default")
      (node (ref "C16") (pin "1") (pinfunction "1_1") (pintype "passive"))
      (node (ref "C19") (pin "1") (pinfunction "1_1") (pintype "passive"))
      (node (ref "L1") (pin "2") (pinfunction "2_2") (pintype "passive"))
      (node (ref "R8") (pin "2") (pinfunction "2_2") (pintype "passive"))
      (node (ref "TP9") (pin "1") (pintype "passive"))
    )
    (net (code "10") (name "Net-(C22-Pad2)") (class "Default")
      (node (ref "C22") (pin "2") (pinfunction "2_2") (pintype "passive"))
      (node (ref "R23") (pin "1") (pinfunction "1_1") (pintype "passive"))
    )
    (net (code "11") (name "Net-(D1-A)") (class "Default")
      (node (ref "D1") (pin "2") (pinfunction "A_2") (pintype "passive"))
      (node (ref "T1") (pin "14") (pinfunction "14_14") (pintype "passive"))
    )
    (net (code "12") (name "Net-(D3-K)") (class "Default")
      (node (ref "D3") (pin "1") (pinfunction "K_1") (pintype "passive"))
      (node (ref "D5") (pin "1") (pinfunction "K_1") (pintype "passive"))
      (node (ref "R1") (pin "1") (pinfunction "1_1") (pintype "passive"))
    )
    (net (code "13") (name "Net-(D4-A)") (class "Default")
      (node (ref "D4") (pin "2") (pinfunction "A_2") (pintype "passive"))
      (node (ref "T1") (pin "12") (pinfunction "12_12") (pintype "passive"))
    )
    (net (code "14") (name "Net-(D5-A)") (class "Default")
      (node (ref "D5") (pin "2") (pinfunction "A_2") (pintype "passive"))
      (node (ref "R5") (pin "2") (pinfunction "2_2") (pintype "passive"))
    )
    (net (code "15") (name "Net-(D7-A)") (class "Default")
      (node (ref "D7") (pin "2") (pinfunction "A_2") (pintype "passive"))
      (node (ref "T1") (pin "10") (pinfunction "10_10") (pintype "passive"))
      (node (ref "T1") (pin "11") (pinfunction "11_11") (pintype "passive"))
    )
    (net (code "16") (name "Net-(D8-A)") (class "Default")
      (node (ref "D8") (pin "2") (pinfunction "A_2") (pintype "passive"))
      (node (ref "R6") (pin "1") (pinfunction "1_1") (pintype "passive"))
    )
    (net (code "17") (name "Net-(D8-K)") (class "Default")
      (node (ref "C11") (pin "1") (pinfunction "1_1") (pintype "passive"))
      (node (ref "C17") (pin "1") (pinfunction "1_1") (pintype "passive"))
      (node (ref "C18") (pin "1") (pinfunction "1_1") (pintype "passive"))
      (node (ref "D8") (pin "1") (pinfunction "K_1") (pintype "passive"))
      (node (ref "R10") (pin "2") (pinfunction "2_2") (pintype "passive"))
      (node (ref "R4") (pin "1") (pinfunction "1_1") (pintype "passive"))
      (node (ref "U2") (pin "2") (pinfunction "VDD_2") (pintype "power_in"))
    )
    (net (code "18") (name "Net-(Q1-D)") (class "Default")
      (node (ref "Q1") (pin "2") (pinfunction "D_2") (pintype "passive"))
      (node (ref "R5") (pin "1") (pinfunction "1_1") (pintype "passive"))
      (node (ref "T1") (pin "4") (pinfunction "4_4") (pintype "passive"))
    )
    (net (code "19") (name "Net-(Q1-G)") (class "Default")
      (node (ref "Q1") (pin "1") (pinfunction "G_1") (pintype "passive"))
      (node (ref "R19") (pin "2") (pinfunction "2_2") (pintype "passive"))
    )
    (net (code "20") (name "Net-(Q1-S)") (class "Default")
      (node (ref "Q1") (pin "3") (pinfunction "S_3") (pintype "passive"))
      (node (ref "R22") (pin "1") (pinfunction "1_1") (pintype "passive"))
      (node (ref "R25") (pin "2") (pinfunction "2_2") (pintype "passive"))
      (node (ref "R26") (pin "2") (pinfunction "2_2") (pintype "passive"))
    )
    (net (code "21") (name "Net-(Q2-B)") (class "Default")
      (node (ref "Q2") (pin "1") (pinfunction "B_1") (pintype "passive"))
      (node (ref "Q3") (pin "1") (pinfunction "B_1") (pintype "passive"))
      (node (ref "Q3") (pin "3") (pinfunction "C_3") (pintype "passive"))
      (node (ref "R24") (pin "2") (pinfunction "2_2") (pintype "passive"))
    )
    (net (code "22") (name "Net-(Q2-C)") (class "Default")
      (node (ref "C24") (pin "2") (pinfunction "2_2") (pintype "passive"))
      (node (ref "Q2") (pin "3") (pinfunction "C_3") (pintype "passive"))
      (node (ref "R27") (pin "1") (pinfunction "1_1") (pintype "passive"))
      (node (ref "R29") (pin "1") (pinfunction "1_1") (pintype "passive"))
    )
    (net (code "23") (name "Net-(Q2-E)") (class "Default")
      (node (ref "Q2") (pin "2") (pinfunction "E_2") (pintype "passive"))
      (node (ref "R15") (pin "1") (pinfunction "1_1") (pintype "passive"))
    )
    (net (code "24") (name "Net-(Q3-E)") (class "Default")
      (node (ref "Q3") (pin "2") (pinfunction "E_2") (pintype "passive"))
      (node (ref "R16") (pin "1") (pinfunction "1_1") (pintype "passive"))
    )
    (net (code "25") (name "Net-(R2-Pad1)") (class "Default")
      (node (ref "R2") (pin "1") (pinfunction "1_1") (pintype "passive"))
      (node (ref "R3") (pin "2") (pinfunction "2_2") (pintype "passive"))
    )
    (net (code "26") (name "Net-(R3-Pad1)") (class "Default")
      (node (ref "R3") (pin "1") (pinfunction "1_1") (pintype "passive"))
      (node (ref "R4") (pin "2") (pinfunction "2_2") (pintype "passive"))
    )
    (net (code "27") (name "Net-(R10-Pad1)") (class "Default")
      (node (ref "R10") (pin "1") (pinfunction "1_1") (pintype "passive"))
      (node (ref "R11") (pin "2") (pinfunction "2_2") (pintype "passive"))
      (node (ref "R15") (pin "2") (pinfunction "2_2") (pintype "passive"))
    )
    (net (code "28") (name "Net-(R11-Pad1)") (class "Default")
      (node (ref "R11") (pin "1") (pinfunction "1_1") (pintype "passive"))
      (node (ref "R12") (pin "2") (pinfunction "2_2") (pintype "passive"))
      (node (ref "R16") (pin "2") (pinfunction "2_2") (pintype "passive"))
      (node (ref "R7") (pin "2") (pinfunction "2_2") (pintype "passive"))
    )
    (net (code "29") (name "Net-(R12-Pad1)") (class "Default")
      (node (ref "R12") (pin "1") (pinfunction "1_1") (pintype "passive"))
      (node (ref "R17") (pin "1") (pinfunction "1_1") (pintype "passive"))
      (node (ref "R18") (pin "2") (pinfunction "2_2") (pintype "passive"))
      (node (ref "R9") (pin "1") (pinfunction "1_1") (pintype "passive"))
      (node (ref "TP11") (pin "1") (pintype "passive"))
    )
    (net (code "30") (name "Net-(R13-Pad2)") (class "Default")
      (node (ref "R13") (pin "2") (pinfunction "2_2") (pintype "passive"))
      (node (ref "R6") (pin "2") (pinfunction "2_2") (pintype "passive"))
      (node (ref "T1") (pin "7") (pinfunction "7_7") (pintype "passive"))
    )
    (net (code "31") (name "Net-(T1-Pad2)") (class "Default")
      (node (ref "T1") (pin "2") (pinfunction "2_2") (pintype "passive"))
      (node (ref "T1") (pin "3") (pinfunction "3_3") (pintype "passive"))
    )
    (net (code "32") (name "Net-(U1-BOOT)") (class "Default")
      (node (ref "C12") (pin "2") (pinfunction "2_2") (pintype "passive"))
      (node (ref "U1") (pin "6") (pinfunction "BOOT_6") (pintype "power_in"))
    )
    (net (code "33") (name "Net-(U1-FB)") (class "Default")
      (node (ref "C15") (pin "2") (pinfunction "2_2") (pintype "passive"))
      (node (ref "R14") (pin "1") (pinfunction "1_1") (pintype "passive"))
      (node (ref "R20") (pin "2") (pinfunction "2_2") (pintype "passive"))
      (node (ref "U1") (pin "4") (pinfunction "FB_4") (pintype "input"))
    )
    (net (code "34") (name "Net-(U1-SW)") (class "Default")
      (node (ref "C12") (pin "1") (pinfunction "1_1") (pintype "passive"))
      (node (ref "L1") (pin "1") (pinfunction "1_1") (pintype "passive"))
      (node (ref "U1") (pin "2") (pinfunction "SW_2") (pintype "power_in"))
    )
    (net (code "35") (name "Net-(U2-CS)") (class "Default")
      (node (ref "C23") (pin "1") (pinfunction "1_1") (pintype "passive"))
      (node (ref "R22") (pin "2") (pinfunction "2_2") (pintype "passive"))
      (node (ref "U2") (pin "4") (pinfunction "CS_4") (pintype "input"))
    )
    (net (code "36") (name "Net-(U2-DRV)") (class "Default")
      (node (ref "R19") (pin "1") (pinfunction "1_1") (pintype "passive"))
      (node (ref "U2") (pin "3") (pinfunction "DRV_3") (pintype "output"))
    )
    (net (code "37") (name "Net-(U2-FB)") (class "Default")
      (node (ref "C24") (pin "1") (pinfunction "1_1") (pintype "passive"))
      (node (ref "C25") (pin "1") (pinfunction "1_1") (pintype "passive"))
      (node (ref "R27") (pin "2") (pinfunction "2_2") (pintype "passive"))
      (node (ref "R30") (pin "2") (pinfunction "2_2") (pintype "passive"))
      (node (ref "U2") (pin "1") (pinfunction "FB_1") (pintype "input"))
    )
    (net (code "38") (name "Net-(U2-VS)") (class "Default")
      (node (ref "C20") (pin "1") (pinfunction "1_1") (pintype "passive"))
      (node (ref "R13") (pin "1") (pinfunction "1_1") (pintype "passive"))
      (node (ref "R21") (pin "2") (pinfunction "2_2") (pintype "passive"))
      (node (ref "U2") (pin "6") (pinfunction "VS_6") (pintype "input"))
    )
    (net (code "39") (name "Net-(U3-CATHODE)") (class "Default")
      (node (ref "C21") (pin "2") (pinfunction "2_2") (pintype "passive"))
      (node (ref "C22") (pin "1") (pinfunction "1_1") (pintype "passive"))
      (node (ref "R17") (pin "2") (pinfunction "2_2") (pintype "passive"))
      (node (ref "R24") (pin "1") (pinfunction "1_1") (pintype "passive"))
      (node (ref "U3") (pin "1") (pinfunction "CATHODE_1") (pintype "passive"))
    )
    (net (code "40") (name "Net-(U3-REF)") (class "Default")
      (node (ref "C21") (pin "1") (pinfunction "1_1") (pintype "passive"))
      (node (ref "R18") (pin "1") (pinfunction "1_1") (pintype "passive"))
      (node (ref "R23") (pin "2") (pinfunction "2_2") (pintype "passive"))
      (node (ref "R28") (pin "2") (pinfunction "2_2") (pintype "passive"))
      (node (ref "U3") (pin "2") (pinfunction "REF_2") (pintype "input"))
    )
    (net (code "41") (name "unconnected-(T1-NC-Pad6)") (class "Default")
      (node (ref "T1") (pin "6") (pinfunction "NC_6") (pintype "passive"))
    )
    (net (code "42") (name "unconnected-(T1-NC-Pad8)") (class "Default")
      (node (ref "T1") (pin "8") (pinfunction "NC_8") (pintype "passive"))
    )
    (net (code "43") (name "unconnected-(U1-EN-Pad5)") (class "Default")
      (node (ref "U1") (pin "5") (pinfunction "EN_5") (pintype "input"))
    )
  )
)
